# IBOARD.net
KiCad netlist of a schematic drawn in Altium Designer
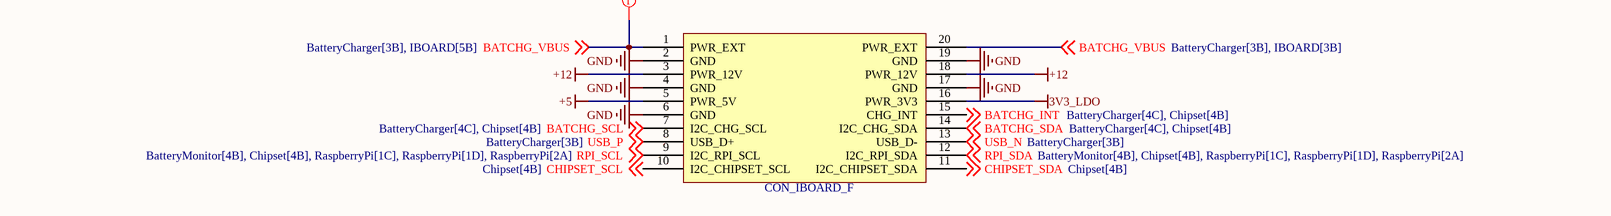
[diagram p0: IBOARD.SchDoc]

(export (version "E")
  (design (tool "Eeschema 10.0.6"))
  (components
    (comp (ref "CON_IBOARD_F")
      (value "I-BOARD")
      (footprint "HC-PM254-8.5H-2x10PS")
      (libsource (lib "IBOARD_Female") (part "I-BOARD"))
    )
  )
  (nets
    (net (code "1") (name "+5") (class "Default")
      (node (ref "CON_IBOARD_F") (pin "5") (pinfunction "PWR_5V_5") (pintype "passive"))
    )
    (net (code "2") (name "+12") (class "Default")
      (node (ref "CON_IBOARD_F") (pin "18") (pinfunction "PWR_12V_18") (pintype "passive"))
      (node (ref "CON_IBOARD_F") (pin "3") (pinfunction "PWR_12V_3") (pintype "passive"))
    )
    (net (code "3") (name "3V3_LDO") (class "Default")
      (node (ref "CON_IBOARD_F") (pin "16") (pinfunction "PWR_3V3_16") (pintype "passive"))
    )
    (net (code "4") (name "BATCHG_INT") (class "Default")
      (node (ref "CON_IBOARD_F") (pin "15") (pinfunction "CHG_INT_15") (pintype "passive"))
    )
    (net (code "5") (name "BATCHG_SCL") (class "Default")
      (node (ref "CON_IBOARD_F") (pin "7") (pinfunction "I2C_CHG_SCL_7") (pintype "passive"))
    )
    (net (code "6") (name "BATCHG_SDA") (class "Default")
      (node (ref "CON_IBOARD_F") (pin "14") (pinfunction "I2C_CHG_SDA_14") (pintype "passive"))
    )
    (net (code "7") (name "BATCHG_VBUS") (class "Default")
      (node (ref "CON_IBOARD_F") (pin "1") (pinfunction "PWR_EXT_1") (pintype "passive"))
      (node (ref "CON_IBOARD_F") (pin "20") (pinfunction "PWR_EXT_20") (pintype "passive"))
    )
    (net (code "8") (name "CHIPSET_SCL") (class "Default")
      (node (ref "CON_IBOARD_F") (pin "10") (pinfunction "I2C_CHIPSET_SCL_10") (pintype "passive"))
    )
    (net (code "9") (name "CHIPSET_SDA") (class "Default")
      (node (ref "CON_IBOARD_F") (pin "11") (pinfunction "I2C_CHIPSET_SDA_11") (pintype "passive"))
    )
    (net (code "10") (name "GND") (class "Default")
      (node (ref "CON_IBOARD_F") (pin "17") (pinfunction "GND_17") (pintype "passive"))
      (node (ref "CON_IBOARD_F") (pin "19") (pinfunction "GND_19") (pintype "passive"))
      (node (ref "CON_IBOARD_F") (pin "2") (pinfunction "GND_2") (pintype "passive"))
      (node (ref "CON_IBOARD_F") (pin "4") (pinfunction "GND_4") (pintype "passive"))
      (node (ref "CON_IBOARD_F") (pin "6") (pinfunction "GND_6") (pintype "passive"))
    )
    (net (code "11") (name "RPI_SCL") (class "Default")
      (node (ref "CON_IBOARD_F") (pin "9") (pinfunction "I2C_RPI_SCL_9") (pintype "passive"))
    )
    (net (code "12") (name "RPI_SDA") (class "Default")
      (node (ref "CON_IBOARD_F") (pin "12") (pinfunction "I2C_RPI_SDA_12") (pintype "passive"))
    )
    (net (code "13") (name "USB_N") (class "Default")
      (node (ref "CON_IBOARD_F") (pin "13") (pinfunction "USB_D-_13") (pintype "passive"))
    )
    (net (code "14") (name "USB_P") (class "Default")
      (node (ref "CON_IBOARD_F") (pin "8") (pinfunction "USB_D+_8") (pintype "passive"))
    )
  )
)
